# SCH_TestPCB_2024-04-18.net
KiCad netlist of a schematic drawn in EasyEDA
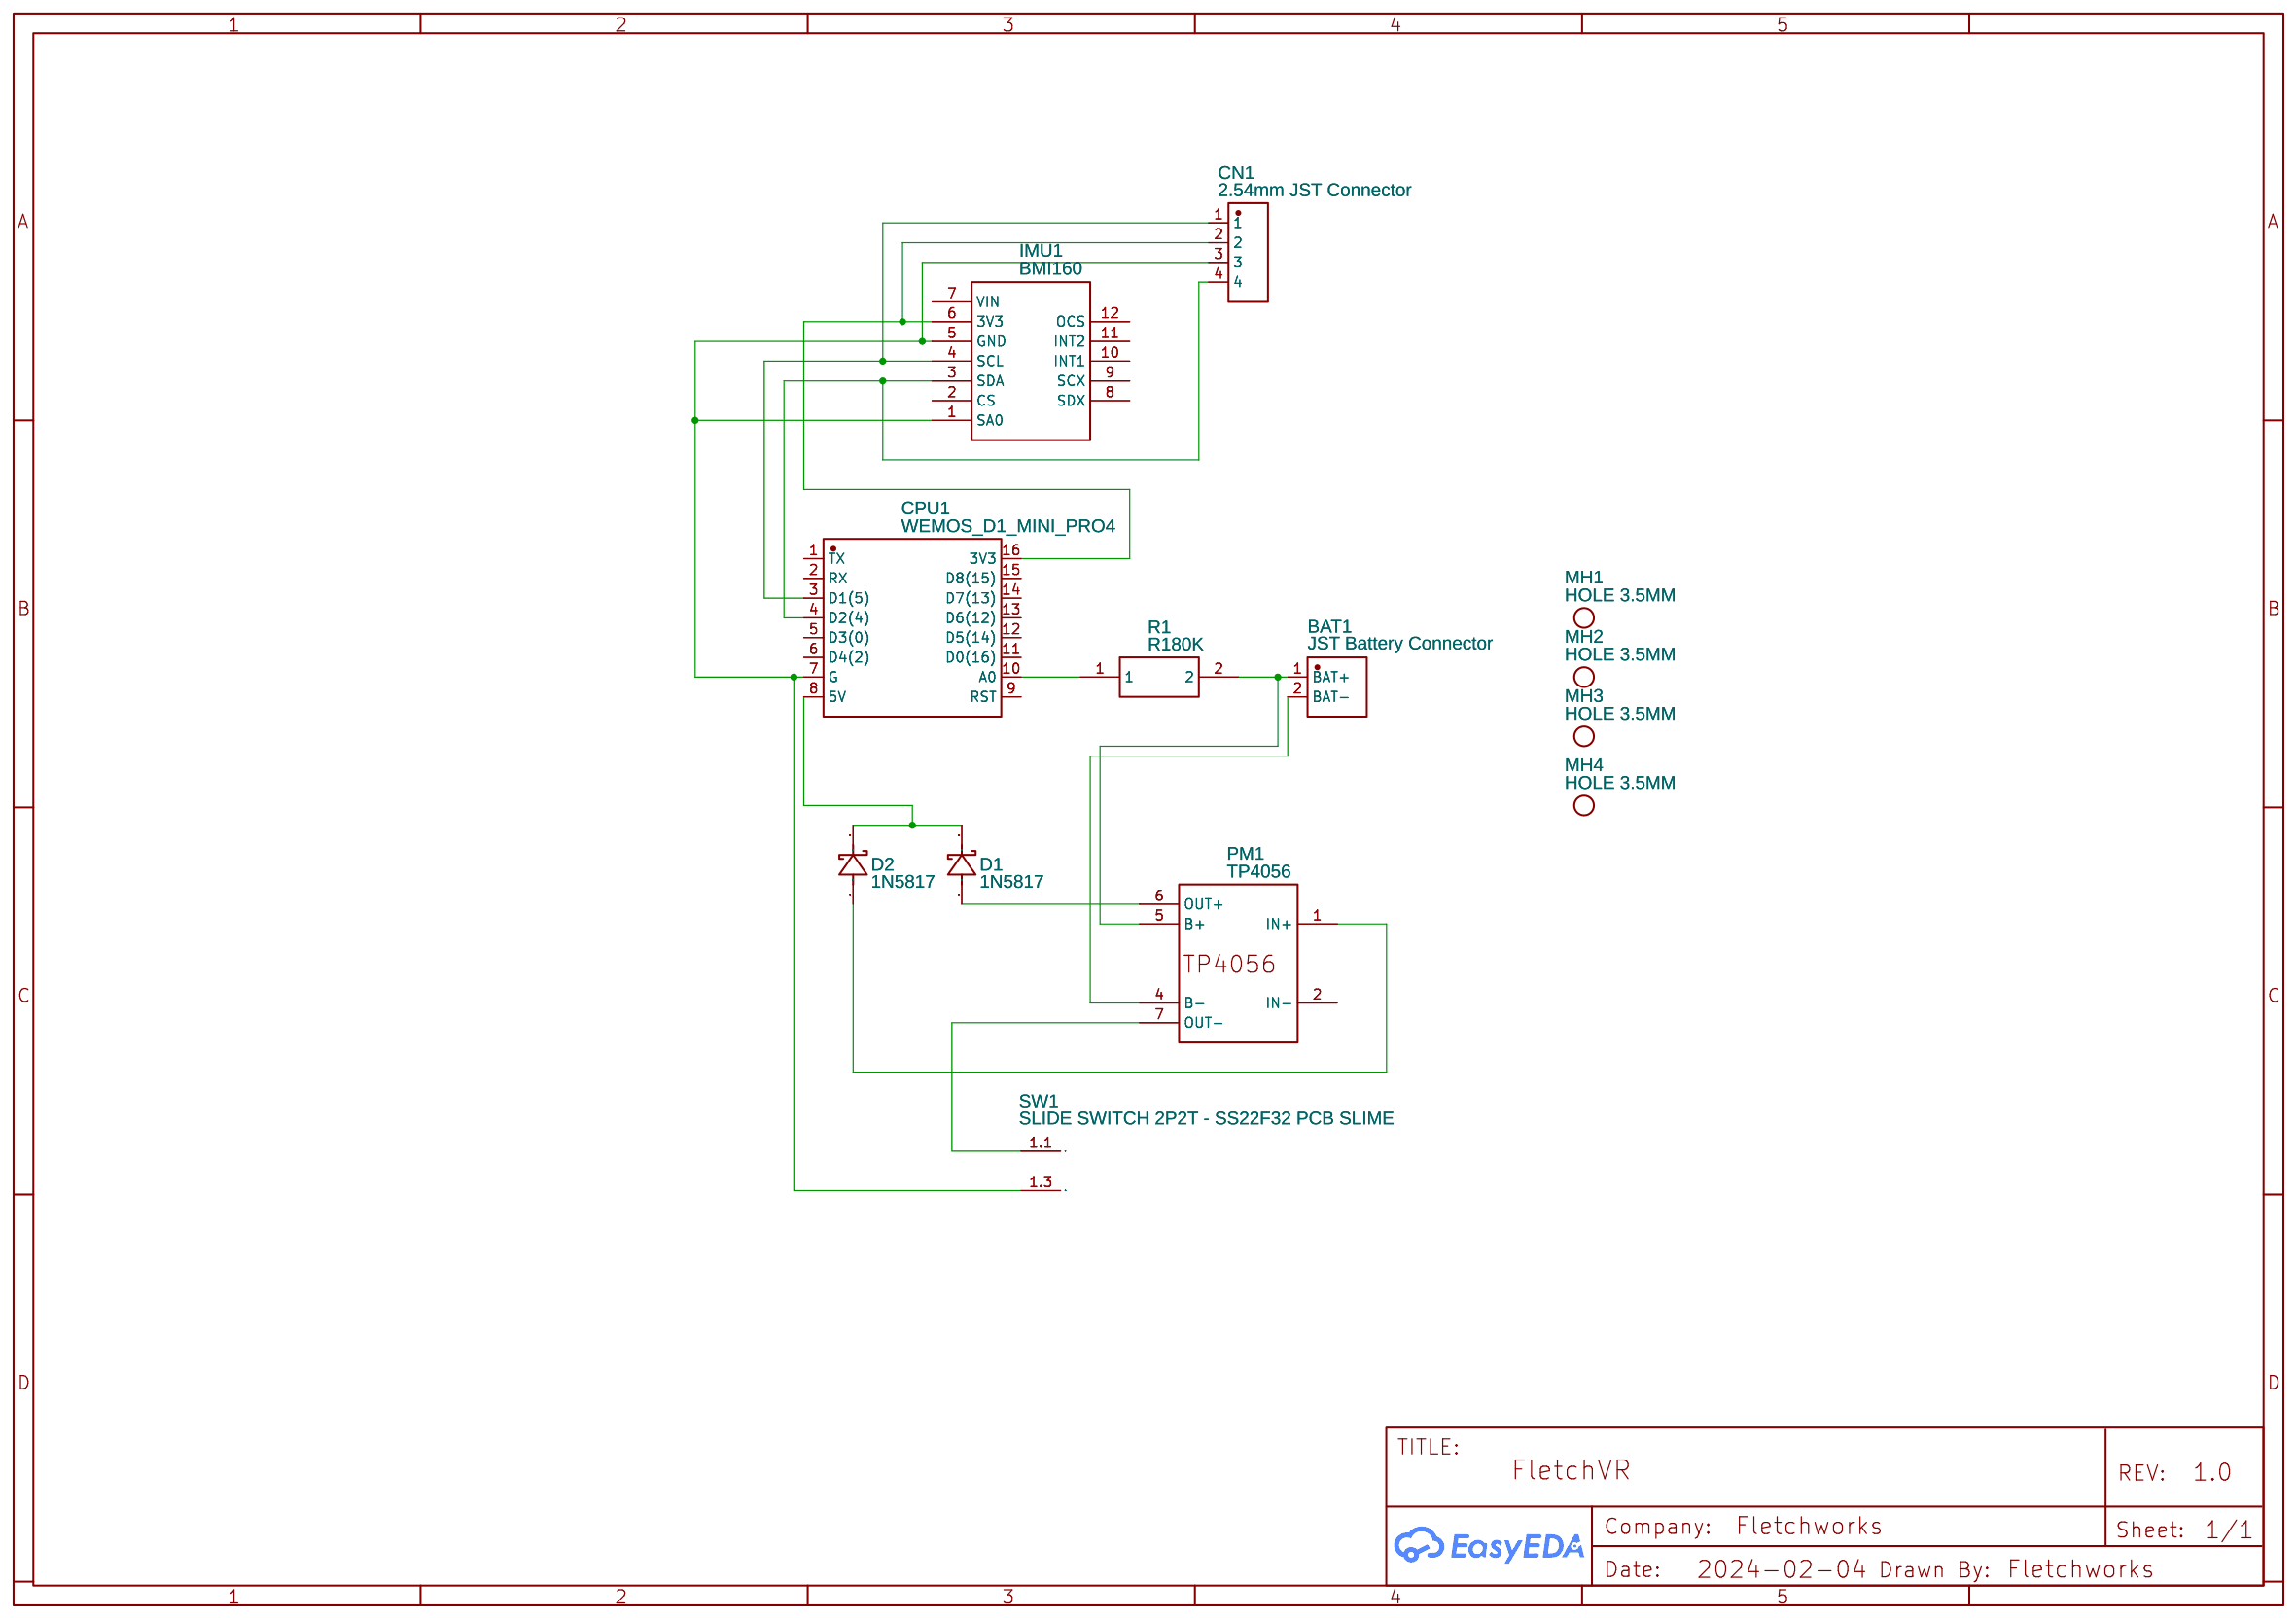
[diagram p0: schematic sheet]

(export (version "E")
  (design (tool "Eeschema 10.0.6"))
  (components
    (comp (ref "BAT1") (value "JST Battery Connector") (libsource (lib "") (part "JST-PH-JST-PH2 COPY")))
    (comp (ref "CN1")
      (value "2.54mm JST Connector")
      (fields (field (name "Manufacturer Part") "XH-AW-2.54MM-4P"))
      (libsource (lib "") (part "XH-AW-2.54MM-4P"))
    )
    (comp (ref "CPU1")
      (value "WEMOS_D1_MINI_PRO4")
      (fields (field (name "Manufacturer Part") "Wemos_D1_mini_Pro4"))
      (libsource (lib "") (part "WEMOS_D1_MINI_PRO4"))
    )
    (comp (ref "D1") (value "1N5817") (libsource (lib "") (part "1N5817")))
    (comp (ref "D2") (value "1N5817") (libsource (lib "") (part "1N5817")))
    (comp (ref "IMU1") (value "BMI160") (libsource (lib "") (part "BMI160")))
    (comp (ref "MH1") (value "HOLE 3.5MM") (libsource (lib "") (part "HOLE 3.5MM")))
    (comp (ref "MH2") (value "HOLE 3.5MM") (libsource (lib "") (part "HOLE 3.5MM")))
    (comp (ref "MH3") (value "HOLE 3.5MM") (libsource (lib "") (part "HOLE 3.5MM")))
    (comp (ref "MH4") (value "HOLE 3.5MM") (libsource (lib "") (part "HOLE 3.5MM")))
    (comp (ref "PM1")
      (value "TP4056")
      (fields (field (name "Manufacturer Part") "TP4056-protect"))
      (libsource (lib "") (part "TP4056-siz"))
    )
    (comp (ref "R1") (value "R180K") (libsource (lib "") (part "R180K")))
    (comp (ref "SW1")
      (value "SLIDE SWITCH 2P2T - SS22F32 PCB SLIME")
      (fields (field (name "Manufacturer Part") "SS22F32"))
      (libsource (lib "") (part "SLIDE SWITCH 2P2T - SS22F32 PCB SLIME"))
    )
  )
  (nets
    (net (code "1") (name "Net-(BAT1-BAT+)") (class "Default")
      (node (ref "BAT1") (pin "1") (pinfunction "BAT+_1") (pintype "unspecified"))
      (node (ref "PM1") (pin "5") (pinfunction "B+_5") (pintype "unspecified"))
      (node (ref "R1") (pin "2") (pinfunction "2_2") (pintype "unspecified"))
    )
    (net (code "2") (name "Net-(BAT1-BAT-)") (class "Default")
      (node (ref "BAT1") (pin "2") (pinfunction "BAT-_2") (pintype "unspecified"))
      (node (ref "PM1") (pin "4") (pinfunction "B-_4") (pintype "unspecified"))
    )
    (net (code "3") (name "Net-(CPU1-3V3)") (class "Default")
      (node (ref "CN1") (pin "2") (pinfunction "2_2") (pintype "unspecified"))
      (node (ref "CPU1") (pin "16") (pinfunction "3V3_16") (pintype "unspecified"))
      (node (ref "IMU1") (pin "6") (pinfunction "3V3_6") (pintype "unspecified"))
    )
    (net (code "4") (name "Net-(CPU1-5V)") (class "Default")
      (node (ref "CPU1") (pin "8") (pinfunction "5V_8") (pintype "unspecified"))
      (node (ref "D1") (pin "2") (pinfunction "2_2") (pintype "unspecified"))
      (node (ref "D2") (pin "2") (pinfunction "2_2") (pintype "unspecified"))
    )
    (net (code "5") (name "Net-(CPU1-A0)") (class "Default")
      (node (ref "CPU1") (pin "10") (pinfunction "A0_10") (pintype "unspecified"))
      (node (ref "R1") (pin "1") (pinfunction "1_1") (pintype "unspecified"))
    )
    (net (code "6") (name "Net-(CPU1-D1(5))") (class "Default")
      (node (ref "CN1") (pin "1") (pinfunction "1_1") (pintype "unspecified"))
      (node (ref "CPU1") (pin "3") (pinfunction "D1(5)_3") (pintype "unspecified"))
      (node (ref "IMU1") (pin "4") (pinfunction "SCL_4") (pintype "unspecified"))
    )
    (net (code "7") (name "Net-(CPU1-D2(4))") (class "Default")
      (node (ref "CN1") (pin "4") (pinfunction "4_4") (pintype "unspecified"))
      (node (ref "CPU1") (pin "4") (pinfunction "D2(4)_4") (pintype "unspecified"))
      (node (ref "IMU1") (pin "3") (pinfunction "SDA_3") (pintype "unspecified"))
    )
    (net (code "8") (name "Net-(CPU1-G)") (class "Default")
      (node (ref "CN1") (pin "3") (pinfunction "3_3") (pintype "unspecified"))
      (node (ref "CPU1") (pin "7") (pinfunction "G_7") (pintype "unspecified"))
      (node (ref "IMU1") (pin "1") (pinfunction "SA0_1") (pintype "unspecified"))
      (node (ref "IMU1") (pin "5") (pinfunction "GND_5") (pintype "unspecified"))
      (node (ref "SW1") (pin "1.3") (pinfunction "2_1.3") (pintype "unspecified"))
    )
    (net (code "9") (name "Net-(PM1-IN+)") (class "Default")
      (node (ref "D2") (pin "1") (pinfunction "1_1") (pintype "unspecified"))
      (node (ref "PM1") (pin "1") (pinfunction "IN+_1") (pintype "unspecified"))
    )
    (net (code "10") (name "Net-(PM1-OUT+)") (class "Default")
      (node (ref "D1") (pin "1") (pinfunction "1_1") (pintype "unspecified"))
      (node (ref "PM1") (pin "6") (pinfunction "OUT+_6") (pintype "unspecified"))
    )
    (net (code "11") (name "Net-(PM1-OUT-)") (class "Default")
      (node (ref "PM1") (pin "7") (pinfunction "OUT-_7") (pintype "unspecified"))
      (node (ref "SW1") (pin "1.1") (pinfunction "1_1.1") (pintype "unspecified"))
    )
    (net (code "12") (name "unconnected-(CPU1-D0(16)-Pad11)") (class "Default")
      (node (ref "CPU1") (pin "11") (pinfunction "D0(16)_11") (pintype "unspecified"))
    )
    (net (code "13") (name "unconnected-(CPU1-D3(0)-Pad5)") (class "Default")
      (node (ref "CPU1") (pin "5") (pinfunction "D3(0)_5") (pintype "unspecified"))
    )
    (net (code "14") (name "unconnected-(CPU1-D4(2)-Pad6)") (class "Default")
      (node (ref "CPU1") (pin "6") (pinfunction "D4(2)_6") (pintype "unspecified"))
    )
    (net (code "15") (name "unconnected-(CPU1-D5(14)-Pad12)") (class "Default")
      (node (ref "CPU1") (pin "12") (pinfunction "D5(14)_12") (pintype "unspecified"))
    )
    (net (code "16") (name "unconnected-(CPU1-D6(12)-Pad13)") (class "Default")
      (node (ref "CPU1") (pin "13") (pinfunction "D6(12)_13") (pintype "unspecified"))
    )
    (net (code "17") (name "unconnected-(CPU1-D7(13)-Pad14)") (class "Default")
      (node (ref "CPU1") (pin "14") (pinfunction "D7(13)_14") (pintype "unspecified"))
    )
    (net (code "18") (name "unconnected-(CPU1-D8(15)-Pad15)") (class "Default")
      (node (ref "CPU1") (pin "15") (pinfunction "D8(15)_15") (pintype "unspecified"))
    )
    (net (code "19") (name "unconnected-(CPU1-RST-Pad9)") (class "Default")
      (node (ref "CPU1") (pin "9") (pinfunction "RST_9") (pintype "unspecified"))
    )
    (net (code "20") (name "unconnected-(CPU1-RX-Pad2)") (class "Default")
      (node (ref "CPU1") (pin "2") (pinfunction "RX_2") (pintype "unspecified"))
    )
    (net (code "21") (name "unconnected-(CPU1-TX-Pad1)") (class "Default")
      (node (ref "CPU1") (pin "1") (pinfunction "TX_1") (pintype "unspecified"))
    )
    (net (code "22") (name "unconnected-(IMU1-CS-Pad2)") (class "Default")
      (node (ref "IMU1") (pin "2") (pinfunction "CS_2") (pintype "unspecified"))
    )
    (net (code "23") (name "unconnected-(IMU1-INT1-Pad10)") (class "Default")
      (node (ref "IMU1") (pin "10") (pinfunction "INT1_10") (pintype "unspecified"))
    )
    (net (code "24") (name "unconnected-(IMU1-INT2-Pad11)") (class "Default")
      (node (ref "IMU1") (pin "11") (pinfunction "INT2_11") (pintype "unspecified"))
    )
    (net (code "25") (name "unconnected-(IMU1-OCS-Pad12)") (class "Default")
      (node (ref "IMU1") (pin "12") (pinfunction "OCS_12") (pintype "unspecified"))
    )
    (net (code "26") (name "unconnected-(IMU1-SCX-Pad9)") (class "Default")
      (node (ref "IMU1") (pin "9") (pinfunction "SCX_9") (pintype "unspecified"))
    )
    (net (code "27") (name "unconnected-(IMU1-SDX-Pad8)") (class "Default")
      (node (ref "IMU1") (pin "8") (pinfunction "SDX_8") (pintype "unspecified"))
    )
    (net (code "28") (name "unconnected-(IMU1-VIN-Pad7)") (class "Default")
      (node (ref "IMU1") (pin "7") (pinfunction "VIN_7") (pintype "unspecified"))
    )
    (net (code "29") (name "unconnected-(PM1-IN--Pad2)") (class "Default")
      (node (ref "PM1") (pin "2") (pinfunction "IN-_2") (pintype "unspecified"))
    )
  )
)
